# sch6.net
KiCad netlist of a schematic drawn in Altium Designer
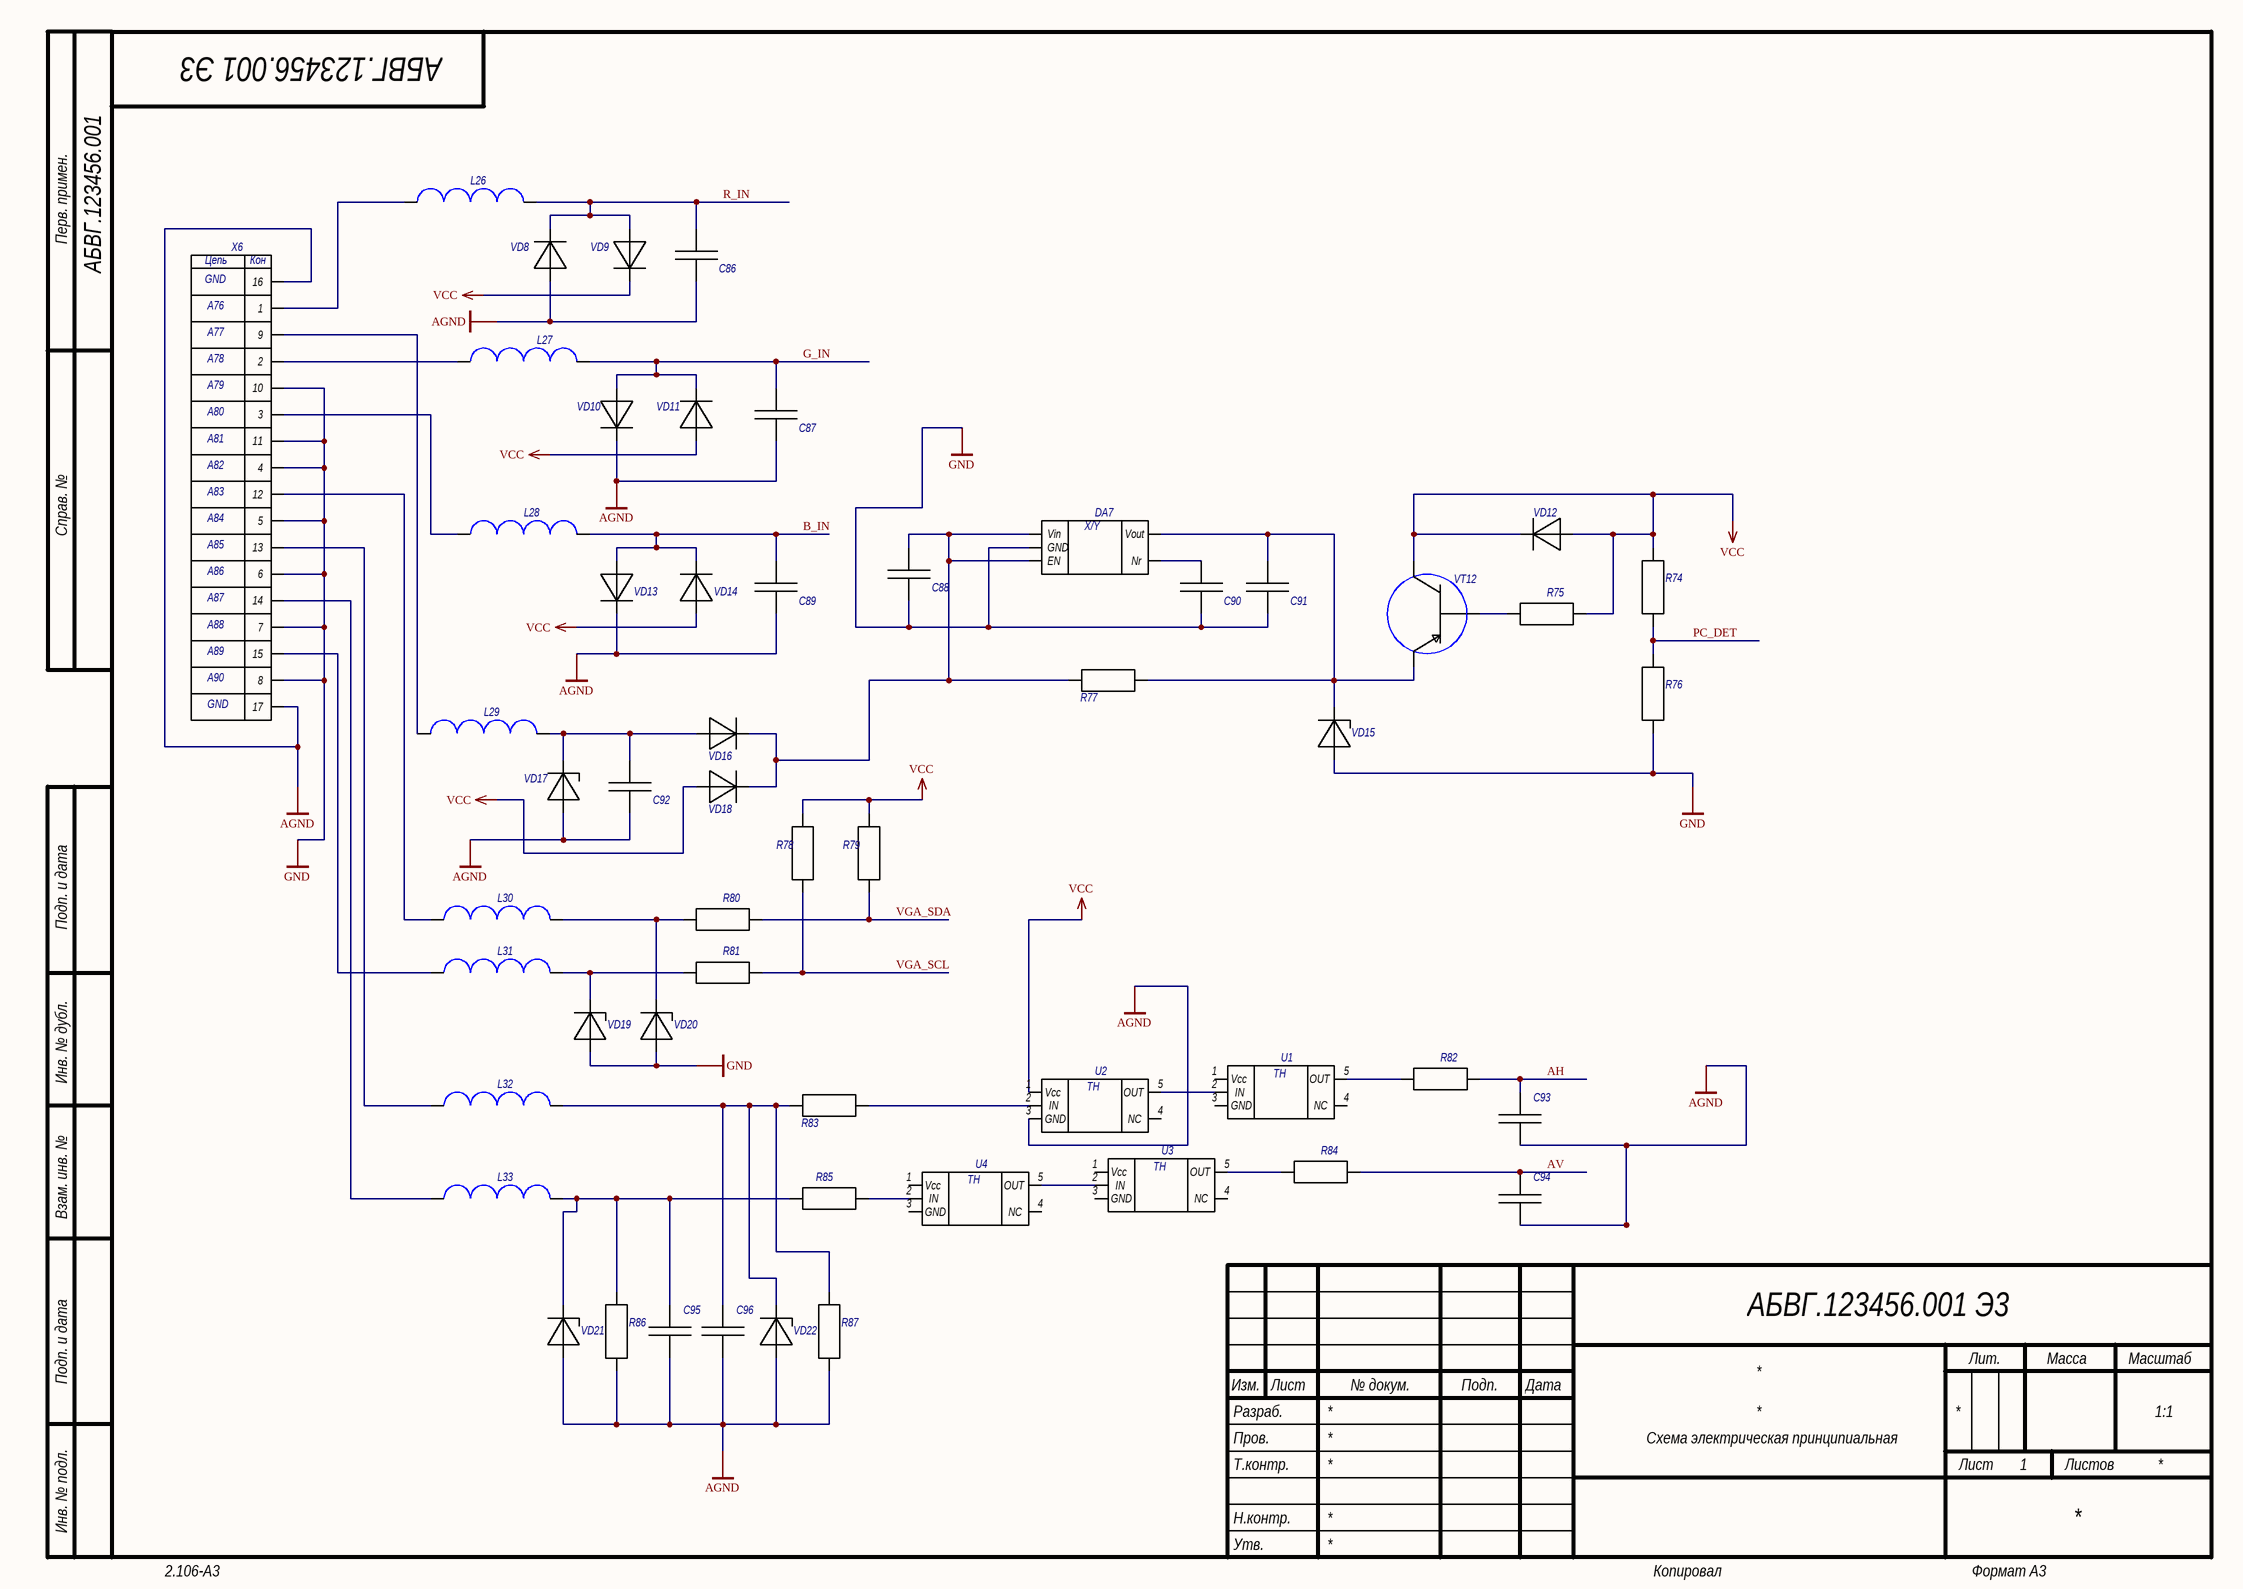
[diagram p0: sch6.SchDoc]

(export (version "E")
  (design (tool "Eeschema 10.0.6"))
  (components
    (comp (ref "C86")
      (value "*")
      (footprint "Capacitor 0805")
      (libsource (lib "k7shared") (part "Capacitor"))
    )
    (comp (ref "C87")
      (value "*")
      (footprint "Capacitor 0805")
      (libsource (lib "k7shared") (part "Capacitor"))
    )
    (comp (ref "C88")
      (value "*")
      (footprint "Capacitor 0805")
      (libsource (lib "k7shared") (part "Capacitor"))
    )
    (comp (ref "C89")
      (value "*")
      (footprint "Capacitor 0805")
      (libsource (lib "k7shared") (part "Capacitor"))
    )
    (comp (ref "C90")
      (value "*")
      (footprint "Capacitor 0805")
      (libsource (lib "k7shared") (part "Capacitor"))
    )
    (comp (ref "C91")
      (value "*")
      (footprint "Capacitor 0805")
      (libsource (lib "k7shared") (part "Capacitor"))
    )
    (comp (ref "C92")
      (value "*")
      (footprint "Capacitor 0805")
      (libsource (lib "k7shared") (part "Capacitor"))
    )
    (comp (ref "C93")
      (value "*")
      (footprint "Capacitor 0805")
      (libsource (lib "k7shared") (part "Capacitor"))
    )
    (comp (ref "C94")
      (value "*")
      (footprint "Capacitor 0805")
      (libsource (lib "k7shared") (part "Capacitor"))
    )
    (comp (ref "C95")
      (value "*")
      (footprint "Capacitor 0805")
      (libsource (lib "k7shared") (part "Capacitor"))
    )
    (comp (ref "C96")
      (value "*")
      (footprint "Capacitor 0805")
      (libsource (lib "k7shared") (part "Capacitor"))
    )
    (comp (ref "DA7") (value "*") (footprint "MIC5205") (libsource (lib "k7sch6") (part "MIC52")))
    (comp (ref "L26") (value "*") (footprint "Inductor 2520") (libsource (lib "k7shared") (part "Inductor")))
    (comp (ref "L27") (value "*") (footprint "Inductor 2520") (libsource (lib "k7shared") (part "Inductor")))
    (comp (ref "L28") (value "*") (footprint "Inductor 2520") (libsource (lib "k7shared") (part "Inductor")))
    (comp (ref "L29") (value "*") (footprint "Inductor 2520") (libsource (lib "k7shared") (part "Inductor")))
    (comp (ref "L30") (value "*") (footprint "Inductor 2520") (libsource (lib "k7shared") (part "Inductor")))
    (comp (ref "L31") (value "*") (footprint "Inductor 2520") (libsource (lib "k7shared") (part "Inductor")))
    (comp (ref "L32") (value "*") (footprint "Inductor 2520") (libsource (lib "k7shared") (part "Inductor")))
    (comp (ref "L33") (value "*") (footprint "Inductor 2520") (libsource (lib "k7shared") (part "Inductor")))
    (comp (ref "R74") (value "*") (footprint "Resistor 1206") (libsource (lib "k7shared") (part "Resistor")))
    (comp (ref "R75") (value "*") (footprint "Resistor 1206") (libsource (lib "k7shared") (part "Resistor")))
    (comp (ref "R76") (value "*") (footprint "Resistor 1206") (libsource (lib "k7shared") (part "Resistor")))
    (comp (ref "R77") (value "*") (footprint "Resistor 1206") (libsource (lib "k7shared") (part "Resistor")))
    (comp (ref "R78") (value "*") (footprint "Resistor 1206") (libsource (lib "k7shared") (part "Resistor")))
    (comp (ref "R79") (value "*") (footprint "Resistor 1206") (libsource (lib "k7shared") (part "Resistor")))
    (comp (ref "R80") (value "*") (footprint "Resistor 1206") (libsource (lib "k7shared") (part "Resistor")))
    (comp (ref "R81") (value "*") (footprint "Resistor 1206") (libsource (lib "k7shared") (part "Resistor")))
    (comp (ref "R82") (value "*") (footprint "Resistor 1206") (libsource (lib "k7shared") (part "Resistor")))
    (comp (ref "R83") (value "*") (footprint "Resistor 1206") (libsource (lib "k7shared") (part "Resistor")))
    (comp (ref "R84") (value "*") (footprint "Resistor 1206") (libsource (lib "k7shared") (part "Resistor")))
    (comp (ref "R85") (value "*") (footprint "Resistor 1206") (libsource (lib "k7shared") (part "Resistor")))
    (comp (ref "R86") (value "*") (footprint "Resistor 1206") (libsource (lib "k7shared") (part "Resistor")))
    (comp (ref "R87") (value "*") (footprint "Resistor 1206") (libsource (lib "k7shared") (part "Resistor")))
    (comp (ref "U1") (value "*") (footprint "MIC5205") (libsource (lib "k7sch6") (part "Schmitt Inv")))
    (comp (ref "U2") (value "*") (footprint "MIC5205") (libsource (lib "k7sch6") (part "Schmitt Inv")))
    (comp (ref "U3") (value "*") (footprint "MIC5205") (libsource (lib "k7sch6") (part "Schmitt Inv")))
    (comp (ref "U4") (value "*") (footprint "MIC5205") (libsource (lib "k7sch6") (part "Schmitt Inv")))
    (comp (ref "VD8") (value "*") (footprint "Diode") (libsource (lib "k7shared") (part "Diode 1")))
    (comp (ref "VD9") (value "*") (footprint "Diode") (libsource (lib "k7shared") (part "Diode 1")))
    (comp (ref "VD10") (value "*") (footprint "Diode") (libsource (lib "k7shared") (part "Diode 1")))
    (comp (ref "VD11") (value "*") (footprint "Diode") (libsource (lib "k7shared") (part "Diode 1")))
    (comp (ref "VD12") (value "*") (footprint "Diode") (libsource (lib "k7shared") (part "Diode 1")))
    (comp (ref "VD13") (value "*") (footprint "Diode") (libsource (lib "k7shared") (part "Diode 1")))
    (comp (ref "VD14") (value "*") (footprint "Diode") (libsource (lib "k7shared") (part "Diode 1")))
    (comp (ref "VD15") (value "*") (footprint "Diode") (libsource (lib "k7shared") (part "Diode 2")))
    (comp (ref "VD16") (value "*") (footprint "Diode") (libsource (lib "k7shared") (part "Diode 1")))
    (comp (ref "VD17") (value "*") (footprint "Diode") (libsource (lib "k7shared") (part "Diode 2")))
    (comp (ref "VD18") (value "*") (footprint "Diode") (libsource (lib "k7shared") (part "Diode 1")))
    (comp (ref "VD19") (value "*") (footprint "Diode") (libsource (lib "k7shared") (part "Diode 2")))
    (comp (ref "VD20") (value "*") (footprint "Diode") (libsource (lib "k7shared") (part "Diode 2")))
    (comp (ref "VD21") (value "*") (footprint "Diode") (libsource (lib "k7shared") (part "Diode 2")))
    (comp (ref "VD22") (value "*") (footprint "Diode") (libsource (lib "k7shared") (part "Diode 2")))
    (comp (ref "VT12")
      (value "*")
      (footprint "Transistor 1")
      (libsource (lib "k7shared") (part "Transistor 2"))
    )
    (comp (ref "X6")
      (value "*")
      (footprint "VGA Connector")
      (libsource (lib "k7sch6") (part "VGA connector"))
    )
  )
  (nets
    (net (code "1") (name "/AH") (class "Default")
      (node (ref "C93") (pin "2") (pinfunction "2_2") (pintype "passive"))
      (node (ref "R82") (pin "2") (pinfunction "2_2") (pintype "passive"))
    )
    (net (code "2") (name "/AV") (class "Default")
      (node (ref "C94") (pin "2") (pinfunction "2_2") (pintype "passive"))
      (node (ref "R84") (pin "2") (pinfunction "2_2") (pintype "passive"))
    )
    (net (code "3") (name "/B_IN") (class "Default")
      (node (ref "C89") (pin "2") (pinfunction "2_2") (pintype "passive"))
      (node (ref "L28") (pin "2") (pinfunction "2_2") (pintype "passive"))
      (node (ref "VD13") (pin "1") (pinfunction "1_1") (pintype "passive"))
      (node (ref "VD14") (pin "2") (pinfunction "2_2") (pintype "passive"))
    )
    (net (code "4") (name "/G_IN") (class "Default")
      (node (ref "C87") (pin "2") (pinfunction "2_2") (pintype "passive"))
      (node (ref "L27") (pin "2") (pinfunction "2_2") (pintype "passive"))
      (node (ref "VD10") (pin "1") (pinfunction "1_1") (pintype "passive"))
      (node (ref "VD11") (pin "2") (pinfunction "2_2") (pintype "passive"))
    )
    (net (code "5") (name "/PC_DET") (class "Default")
      (node (ref "R74") (pin "1") (pinfunction "1_1") (pintype "passive"))
      (node (ref "R76") (pin "2") (pinfunction "2_2") (pintype "passive"))
    )
    (net (code "6") (name "/R_IN") (class "Default")
      (node (ref "C86") (pin "2") (pinfunction "2_2") (pintype "passive"))
      (node (ref "L26") (pin "2") (pinfunction "2_2") (pintype "passive"))
      (node (ref "VD8") (pin "2") (pinfunction "2_2") (pintype "passive"))
      (node (ref "VD9") (pin "1") (pinfunction "1_1") (pintype "passive"))
    )
    (net (code "7") (name "/VGA_SCL") (class "Default")
      (node (ref "R78") (pin "1") (pinfunction "1_1") (pintype "passive"))
      (node (ref "R81") (pin "2") (pinfunction "2_2") (pintype "passive"))
    )
    (net (code "8") (name "/VGA_SDA") (class "Default")
      (node (ref "R79") (pin "1") (pinfunction "1_1") (pintype "passive"))
      (node (ref "R80") (pin "2") (pinfunction "2_2") (pintype "passive"))
    )
    (net (code "9") (name "AGND") (class "Default")
      (node (ref "C86") (pin "1") (pinfunction "1_1") (pintype "passive"))
      (node (ref "C87") (pin "1") (pinfunction "1_1") (pintype "passive"))
      (node (ref "C89") (pin "1") (pinfunction "1_1") (pintype "passive"))
      (node (ref "C92") (pin "1") (pinfunction "1_1") (pintype "passive"))
      (node (ref "C93") (pin "1") (pinfunction "1_1") (pintype "passive"))
      (node (ref "C94") (pin "1") (pinfunction "1_1") (pintype "passive"))
      (node (ref "C95") (pin "1") (pinfunction "1_1") (pintype "passive"))
      (node (ref "C96") (pin "1") (pinfunction "1_1") (pintype "passive"))
      (node (ref "R86") (pin "1") (pinfunction "1_1") (pintype "passive"))
      (node (ref "R87") (pin "1") (pinfunction "1_1") (pintype "passive"))
      (node (ref "U2") (pin "3") (pinfunction "GND_3") (pintype "passive"))
      (node (ref "VD10") (pin "2") (pinfunction "2_2") (pintype "passive"))
      (node (ref "VD13") (pin "2") (pinfunction "2_2") (pintype "passive"))
      (node (ref "VD17") (pin "1") (pinfunction "1_1") (pintype "passive"))
      (node (ref "VD21") (pin "1") (pinfunction "1_1") (pintype "passive"))
      (node (ref "VD22") (pin "1") (pinfunction "1_1") (pintype "passive"))
      (node (ref "VD8") (pin "1") (pinfunction "1_1") (pintype "passive"))
      (node (ref "X6") (pin "16") (pinfunction "16_16") (pintype "passive"))
      (node (ref "X6") (pin "17") (pinfunction "17_17") (pintype "passive"))
    )
    (net (code "10") (name "GND") (class "Default")
      (node (ref "C88") (pin "1") (pinfunction "1_1") (pintype "passive"))
      (node (ref "C90") (pin "1") (pinfunction "1_1") (pintype "passive"))
      (node (ref "C91") (pin "1") (pinfunction "1_1") (pintype "passive"))
      (node (ref "DA7") (pin "2") (pinfunction "GND_2") (pintype "passive"))
      (node (ref "R76") (pin "1") (pinfunction "1_1") (pintype "passive"))
      (node (ref "VD15") (pin "1") (pinfunction "1_1") (pintype "passive"))
      (node (ref "VD19") (pin "1") (pinfunction "1_1") (pintype "passive"))
      (node (ref "VD20") (pin "1") (pinfunction "1_1") (pintype "passive"))
      (node (ref "X6") (pin "10") (pinfunction "10_10") (pintype "passive"))
      (node (ref "X6") (pin "11") (pinfunction "11_11") (pintype "passive"))
      (node (ref "X6") (pin "4") (pinfunction "4_4") (pintype "passive"))
      (node (ref "X6") (pin "5") (pinfunction "5_5") (pintype "passive"))
      (node (ref "X6") (pin "6") (pinfunction "6_6") (pintype "passive"))
      (node (ref "X6") (pin "7") (pinfunction "7_7") (pintype "passive"))
      (node (ref "X6") (pin "8") (pinfunction "8_8") (pintype "passive"))
    )
    (net (code "11") (name "Net-(C92-Pad2)") (class "Default")
      (node (ref "C92") (pin "2") (pinfunction "2_2") (pintype "passive"))
      (node (ref "L29") (pin "2") (pinfunction "2_2") (pintype "passive"))
      (node (ref "VD16") (pin "1") (pinfunction "1_1") (pintype "passive"))
      (node (ref "VD17") (pin "2") (pinfunction "2_2") (pintype "passive"))
    )
    (net (code "12") (name "Net-(C95-Pad2)") (class "Default")
      (node (ref "C95") (pin "2") (pinfunction "2_2") (pintype "passive"))
      (node (ref "L33") (pin "2") (pinfunction "2_2") (pintype "passive"))
      (node (ref "R85") (pin "1") (pinfunction "1_1") (pintype "passive"))
      (node (ref "R86") (pin "2") (pinfunction "2_2") (pintype "passive"))
      (node (ref "VD21") (pin "2") (pinfunction "2_2") (pintype "passive"))
    )
    (net (code "13") (name "Net-(C96-Pad2)") (class "Default")
      (node (ref "C96") (pin "2") (pinfunction "2_2") (pintype "passive"))
      (node (ref "L32") (pin "2") (pinfunction "2_2") (pintype "passive"))
      (node (ref "R83") (pin "1") (pinfunction "1_1") (pintype "passive"))
      (node (ref "R87") (pin "2") (pinfunction "2_2") (pintype "passive"))
      (node (ref "VD22") (pin "2") (pinfunction "2_2") (pintype "passive"))
    )
    (net (code "14") (name "Net-(DA7-EN)") (class "Default")
      (node (ref "C88") (pin "2") (pinfunction "2_2") (pintype "passive"))
      (node (ref "DA7") (pin "1") (pinfunction "Vin_1") (pintype "passive"))
      (node (ref "DA7") (pin "3") (pinfunction "EN_3") (pintype "passive"))
      (node (ref "R77") (pin "1") (pinfunction "1_1") (pintype "passive"))
      (node (ref "VD16") (pin "2") (pinfunction "2_2") (pintype "passive"))
      (node (ref "VD18") (pin "2") (pinfunction "2_2") (pintype "passive"))
    )
    (net (code "15") (name "Net-(DA7-Nr)") (class "Default")
      (node (ref "C90") (pin "2") (pinfunction "2_2") (pintype "passive"))
      (node (ref "DA7") (pin "4") (pinfunction "Nr_4") (pintype "passive"))
    )
    (net (code "16") (name "Net-(DA7-Vout)") (class "Default")
      (node (ref "C91") (pin "2") (pinfunction "2_2") (pintype "passive"))
      (node (ref "DA7") (pin "5") (pinfunction "Vout_5") (pintype "passive"))
      (node (ref "R77") (pin "2") (pinfunction "2_2") (pintype "passive"))
      (node (ref "VD15") (pin "2") (pinfunction "2_2") (pintype "passive"))
      (node (ref "VT12") (pin "2") (pinfunction "EMITTER_2") (pintype "passive"))
    )
    (net (code "17") (name "Net-(L26-Pad1)") (class "Default")
      (node (ref "L26") (pin "1") (pinfunction "1_1") (pintype "passive"))
      (node (ref "X6") (pin "1") (pinfunction "1_1") (pintype "passive"))
    )
    (net (code "18") (name "Net-(L27-Pad1)") (class "Default")
      (node (ref "L27") (pin "1") (pinfunction "1_1") (pintype "passive"))
      (node (ref "X6") (pin "2") (pinfunction "2_2") (pintype "passive"))
    )
    (net (code "19") (name "Net-(L28-Pad1)") (class "Default")
      (node (ref "L28") (pin "1") (pinfunction "1_1") (pintype "passive"))
      (node (ref "X6") (pin "3") (pinfunction "3_3") (pintype "passive"))
    )
    (net (code "20") (name "Net-(L29-Pad1)") (class "Default")
      (node (ref "L29") (pin "1") (pinfunction "1_1") (pintype "passive"))
      (node (ref "X6") (pin "9") (pinfunction "9_9") (pintype "passive"))
    )
    (net (code "21") (name "Net-(L30-Pad1)") (class "Default")
      (node (ref "L30") (pin "1") (pinfunction "1_1") (pintype "passive"))
      (node (ref "X6") (pin "12") (pinfunction "12_12") (pintype "passive"))
    )
    (net (code "22") (name "Net-(L30-Pad2)") (class "Default")
      (node (ref "L30") (pin "2") (pinfunction "2_2") (pintype "passive"))
      (node (ref "R80") (pin "1") (pinfunction "1_1") (pintype "passive"))
      (node (ref "VD20") (pin "2") (pinfunction "2_2") (pintype "passive"))
    )
    (net (code "23") (name "Net-(L31-Pad1)") (class "Default")
      (node (ref "L31") (pin "1") (pinfunction "1_1") (pintype "passive"))
      (node (ref "X6") (pin "15") (pinfunction "15_15") (pintype "passive"))
    )
    (net (code "24") (name "Net-(L31-Pad2)") (class "Default")
      (node (ref "L31") (pin "2") (pinfunction "2_2") (pintype "passive"))
      (node (ref "R81") (pin "1") (pinfunction "1_1") (pintype "passive"))
      (node (ref "VD19") (pin "2") (pinfunction "2_2") (pintype "passive"))
    )
    (net (code "25") (name "Net-(L32-Pad1)") (class "Default")
      (node (ref "L32") (pin "1") (pinfunction "1_1") (pintype "passive"))
      (node (ref "X6") (pin "13") (pinfunction "13_13") (pintype "passive"))
    )
    (net (code "26") (name "Net-(L33-Pad1)") (class "Default")
      (node (ref "L33") (pin "1") (pinfunction "1_1") (pintype "passive"))
      (node (ref "X6") (pin "14") (pinfunction "14_14") (pintype "passive"))
    )
    (net (code "27") (name "Net-(U1-IN)") (class "Default")
      (node (ref "U1") (pin "2") (pinfunction "IN_2") (pintype "passive"))
      (node (ref "U2") (pin "5") (pinfunction "OUT_5") (pintype "passive"))
    )
    (net (code "28") (name "Net-(U1-OUT)") (class "Default")
      (node (ref "R82") (pin "1") (pinfunction "1_1") (pintype "passive"))
      (node (ref "U1") (pin "5") (pinfunction "OUT_5") (pintype "passive"))
    )
    (net (code "29") (name "Net-(U2-IN)") (class "Default")
      (node (ref "R83") (pin "2") (pinfunction "2_2") (pintype "passive"))
      (node (ref "U2") (pin "2") (pinfunction "IN_2") (pintype "passive"))
    )
    (net (code "30") (name "Net-(U3-IN)") (class "Default")
      (node (ref "U3") (pin "2") (pinfunction "IN_2") (pintype "passive"))
      (node (ref "U4") (pin "5") (pinfunction "OUT_5") (pintype "passive"))
    )
    (net (code "31") (name "Net-(U3-OUT)") (class "Default")
      (node (ref "R84") (pin "1") (pinfunction "1_1") (pintype "passive"))
      (node (ref "U3") (pin "5") (pinfunction "OUT_5") (pintype "passive"))
    )
    (net (code "32") (name "Net-(U4-IN)") (class "Default")
      (node (ref "R85") (pin "2") (pinfunction "2_2") (pintype "passive"))
      (node (ref "U4") (pin "2") (pinfunction "IN_2") (pintype "passive"))
    )
    (net (code "33") (name "Net-(VT12-BAZA)") (class "Default")
      (node (ref "R75") (pin "1") (pinfunction "1_1") (pintype "passive"))
      (node (ref "VT12") (pin "3") (pinfunction "BAZA_3") (pintype "passive"))
    )
    (net (code "34") (name "VCC") (class "Default")
      (node (ref "R74") (pin "2") (pinfunction "2_2") (pintype "passive"))
      (node (ref "R75") (pin "2") (pinfunction "2_2") (pintype "passive"))
      (node (ref "R78") (pin "2") (pinfunction "2_2") (pintype "passive"))
      (node (ref "R79") (pin "2") (pinfunction "2_2") (pintype "passive"))
      (node (ref "U2") (pin "1") (pinfunction "Vcc_1") (pintype "passive"))
      (node (ref "VD11") (pin "1") (pinfunction "1_1") (pintype "passive"))
      (node (ref "VD12") (pin "1") (pinfunction "1_1") (pintype "passive"))
      (node (ref "VD12") (pin "2") (pinfunction "2_2") (pintype "passive"))
      (node (ref "VD14") (pin "1") (pinfunction "1_1") (pintype "passive"))
      (node (ref "VD18") (pin "1") (pinfunction "1_1") (pintype "passive"))
      (node (ref "VD9") (pin "2") (pinfunction "2_2") (pintype "passive"))
      (node (ref "VT12") (pin "1") (pinfunction "KOLLECTOR_1") (pintype "passive"))
    )
    (net (code "35") (name "unconnected-(U1-GND-Pad3)") (class "Default")
      (node (ref "U1") (pin "3") (pinfunction "GND_3") (pintype "passive"))
    )
    (net (code "36") (name "unconnected-(U1-NC-Pad4)") (class "Default")
      (node (ref "U1") (pin "4") (pinfunction "NC_4") (pintype "passive"))
    )
    (net (code "37") (name "unconnected-(U1-Vcc-Pad1)") (class "Default")
      (node (ref "U1") (pin "1") (pinfunction "Vcc_1") (pintype "passive"))
    )
    (net (code "38") (name "unconnected-(U2-NC-Pad4)") (class "Default")
      (node (ref "U2") (pin "4") (pinfunction "NC_4") (pintype "passive"))
    )
    (net (code "39") (name "unconnected-(U3-GND-Pad3)") (class "Default")
      (node (ref "U3") (pin "3") (pinfunction "GND_3") (pintype "passive"))
    )
    (net (code "40") (name "unconnected-(U3-NC-Pad4)") (class "Default")
      (node (ref "U3") (pin "4") (pinfunction "NC_4") (pintype "passive"))
    )
    (net (code "41") (name "unconnected-(U3-Vcc-Pad1)") (class "Default")
      (node (ref "U3") (pin "1") (pinfunction "Vcc_1") (pintype "passive"))
    )
    (net (code "42") (name "unconnected-(U4-GND-Pad3)") (class "Default")
      (node (ref "U4") (pin "3") (pinfunction "GND_3") (pintype "passive"))
    )
    (net (code "43") (name "unconnected-(U4-NC-Pad4)") (class "Default")
      (node (ref "U4") (pin "4") (pinfunction "NC_4") (pintype "passive"))
    )
    (net (code "44") (name "unconnected-(U4-Vcc-Pad1)") (class "Default")
      (node (ref "U4") (pin "1") (pinfunction "Vcc_1") (pintype "passive"))
    )
  )
)
